# piezo-button-sheet1.net
KiCad netlist of a schematic drawn in Altium Designer
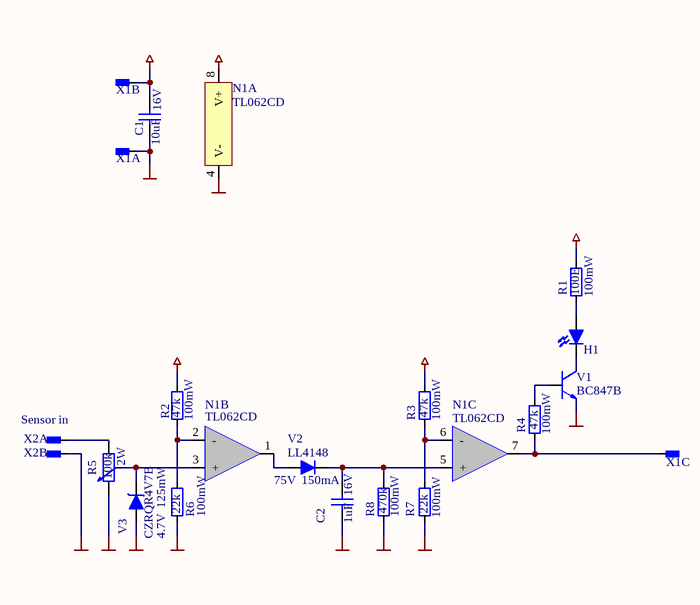
[diagram p0: piezo-button-sheet1.SchDoc]

(export (version "E")
  (design (tool "Eeschema 10.0.6"))
  (components
    (comp (ref "C1")
      (value "C_SMD_CER_10U_16V_10%_X5R_0805")
      (footprint "SMD_0805")
      (description "SMD Capacitor")
      (fields (field (name "ALTIUM_VALUE") "10uF") (field (name "VALUE2") "16V"))
      (libsource (lib "C-Capacitor") (part "C_SMD_CER_10U_16V_10%_X5R_0805"))
    )
    (comp (ref "C2")
      (value "C_SMD_CER_1U_16V_10%_X5R_0603")
      (footprint "SMD_0603")
      (description "SMD Capacitor")
      (fields (field (name "ALTIUM_VALUE") "1uF") (field (name "VALUE2") "16V"))
      (libsource (lib "C-Capacitor") (part "C_SMD_CER_1U_16V_10%_X5R_0603"))
    )
    (comp (ref "H1")
      (value "H_SMD_LED_GREEN_1206")
      (footprint "SMD_1206_BOTTOM_ENTRY")
      (description "LED GREEN CLEAR 1206 REV MT SMD")
      (libsource (lib "H-Signaling device") (part "H_SMD_LED_GREEN_1206"))
    )
    (comp (ref "N1")
      (value "N_TL062CD_SOP-8")
      (footprint "SMD_SOP_8")
      (description "Low-power JFET dual operation amplifier")
      (fields (field (name "TYPE") "TL062CD"))
      (libsource (lib "N-Analog") (part "N_TL062CD_SOP-8"))
    )
    (comp (ref "R1")
      (value "R_SMD_THINFILM_100E_0W1_1%_50PPM_0603")
      (footprint "SMD_0603")
      (description "SMD Resistor")
      (fields (field (name "ALTIUM_VALUE") "100E") (field (name "VALUE2") "100mW"))
      (libsource (lib "R-Resistor") (part "R_SMD_THINFILM_100E_0W1_1%_50PPM_0603"))
    )
    (comp (ref "R2")
      (value "R_SMD_THINFILM_47K_0W1_1%_50PPM_0603")
      (footprint "SMD_0603")
      (description "SMD Resistor")
      (fields (field (name "ALTIUM_VALUE") "47k") (field (name "VALUE2") "100mW"))
      (libsource (lib "R-Resistor") (part "R_SMD_THINFILM_47K_0W1_1%_50PPM_0603"))
    )
    (comp (ref "R3")
      (value "R_SMD_THINFILM_47K_0W1_1%_50PPM_0603")
      (footprint "SMD_0603")
      (description "SMD Resistor")
      (fields (field (name "ALTIUM_VALUE") "47k") (field (name "VALUE2") "100mW"))
      (libsource (lib "R-Resistor") (part "R_SMD_THINFILM_47K_0W1_1%_50PPM_0603"))
    )
    (comp (ref "R4")
      (value "R_SMD_THINFILM_47K_0W1_1%_50PPM_0603")
      (footprint "SMD_0603")
      (description "SMD Resistor")
      (fields (field (name "ALTIUM_VALUE") "47k") (field (name "VALUE2") "100mW"))
      (libsource (lib "R-Resistor") (part "R_SMD_THINFILM_47K_0W1_1%_50PPM_0603"))
    )
    (comp (ref "R5")
      (value "R_THT_POT_100K_2W_10%_150PPM")
      (footprint "THT_CON_P2.54_D0.9_1X3")
      (description "POT 100K OHM 3/4\" RD CERM")
      (fields (field (name "ALTIUM_VALUE") "100k") (field (name "VALUE2") "2W"))
      (libsource (lib "R-Resistor") (part "R_THT_POT_100K_2W_10%_150PPM"))
    )
    (comp (ref "R6")
      (value "R_SMD_THINFILM_22K_0W1_1&_50PPM_0603")
      (footprint "SMD_0603")
      (description "SMD Resistor")
      (fields (field (name "ALTIUM_VALUE") "22k") (field (name "VALUE2") "100mW"))
      (libsource (lib "R-Resistor") (part "R_SMD_THINFILM_22K_0W1_1&_50PPM_0603"))
    )
    (comp (ref "R7")
      (value "R_SMD_THINFILM_22K_0W1_1&_50PPM_0603")
      (footprint "SMD_0603")
      (description "SMD Resistor")
      (fields (field (name "ALTIUM_VALUE") "22k") (field (name "VALUE2") "100mW"))
      (libsource (lib "R-Resistor") (part "R_SMD_THINFILM_22K_0W1_1&_50PPM_0603"))
    )
    (comp (ref "R8")
      (value "R_SMD_THINFILM_470K_0W1_1%_50PPM_0603")
      (footprint "SMD_0603")
      (description "SMD Resistor")
      (fields (field (name "ALTIUM_VALUE") "470k") (field (name "VALUE2") "100mW"))
      (libsource (lib "R-Resistor") (part "R_SMD_THINFILM_470K_0W1_1%_50PPM_0603"))
    )
    (comp (ref "V1")
      (value "V_SMD_TRANS_NPN_BC847B_50V_0A2_SOT-23-3")
      (footprint "SMD_SOT_23_3")
      (description "NPN Transistor")
      (fields (field (name "TYPE") "BC847B"))
      (libsource (lib "V-Semiconductors") (part "V_SMD_TRANS_NPN_BC847B_50V_0A2_SOT-23-3"))
    )
    (comp (ref "V2")
      (value "V_SMD_DIODE_LL4148_75V_0A15_SOD-80")
      (footprint "SMD_SOD_80P")
      (fields
        (field (name "TYPE") "LL4148")
        (field (name "ALTIUM_VALUE") "75V")
        (field (name "VALUE2") "150mA")
      )
      (libsource (lib "V-Semiconductors") (part "V_SMD_DIODE_LL4148_75V_0A15_SOD-80"))
    )
    (comp (ref "V3")
      (value "V_SMD_Z-DIODE_4V7_0W125_0402")
      (footprint "SMD_0402P")
      (description "Zener Diode")
      (fields
        (field (name "TYPE") "CZRQR4V7B")
        (field (name "ALTIUM_VALUE") "4.7V")
        (field (name "VALUE2") "125mW")
      )
      (libsource (lib "V-Semiconductors") (part "V_SMD_Z-DIODE_4V7_0W125_3%_0402"))
    )
    (comp (ref "X1")
      (value "X_CONNECTOR_P2.54_D0.9_1X3")
      (footprint "THT_CON_P2.54_D0.9_1X3")
      (description "Pitch 2.54, Diameter 0.9mm, 1 row, 3 columns")
      (libsource (lib "X-Connectors") (part "X_CONNECTOR_P2.54_D0.9_1X3"))
    )
    (comp (ref "X2")
      (value "X_CONNECTOR_P2.54_D0.9_1X2")
      (footprint "THT_CON_P2.54_D0.9_1X2")
      (description "Pitch 2.54, Diameter 0.9mm, 1 row, 2 columns")
      (libsource (lib "X-Connectors") (part "X_CONNECTOR_P2.54_D0.9_1X2"))
    )
  )
  (nets
    (net (code "1") (name "GND") (class "Default")
      (node (ref "C1") (pin "1") (pinfunction "1_1") (pintype "passive"))
      (node (ref "C2") (pin "1") (pinfunction "1_1") (pintype "passive"))
      (node (ref "N1") (pin "4") (pinfunction "V-_4") (pintype "passive"))
      (node (ref "R5") (pin "1") (pinfunction "NC_1") (pintype "passive"))
      (node (ref "R6") (pin "1") (pinfunction "1_1") (pintype "passive"))
      (node (ref "R7") (pin "1") (pinfunction "1_1") (pintype "passive"))
      (node (ref "R8") (pin "1") (pinfunction "1_1") (pintype "passive"))
      (node (ref "V1") (pin "2") (pinfunction "E_2") (pintype "passive"))
      (node (ref "V3") (pin "1") (pinfunction "1_1") (pintype "passive"))
      (node (ref "X1") (pin "1") (pinfunction "1_1") (pintype "passive"))
      (node (ref "X2") (pin "2") (pinfunction "2_2") (pintype "passive"))
    )
    (net (code "2") (name "Net-(H1-Pad1)") (class "Default")
      (node (ref "H1") (pin "1") (pinfunction "1_1") (pintype "passive"))
      (node (ref "R1") (pin "1") (pinfunction "1_1") (pintype "passive"))
    )
    (net (code "3") (name "Net-(N1B-+)") (class "Default")
      (node (ref "N1") (pin "3") (pinfunction "+_3") (pintype "passive"))
      (node (ref "R5") (pin "2") (pinfunction "NC_2") (pintype "passive"))
      (node (ref "V3") (pin "2") (pinfunction "2_2") (pintype "passive"))
    )
    (net (code "4") (name "Net-(N1B--)") (class "Default")
      (node (ref "N1") (pin "2") (pinfunction "-_2") (pintype "passive"))
      (node (ref "R2") (pin "1") (pinfunction "1_1") (pintype "passive"))
      (node (ref "R6") (pin "2") (pinfunction "2_2") (pintype "passive"))
    )
    (net (code "5") (name "Net-(N1B-OUT-A)") (class "Default")
      (node (ref "N1") (pin "1") (pinfunction "OUT-A_1") (pintype "passive"))
      (node (ref "V2") (pin "1") (pinfunction "1_1") (pintype "passive"))
    )
    (net (code "6") (name "Net-(N1C-+)") (class "Default")
      (node (ref "C2") (pin "2") (pinfunction "2_2") (pintype "passive"))
      (node (ref "N1") (pin "5") (pinfunction "+_5") (pintype "passive"))
      (node (ref "R8") (pin "2") (pinfunction "2_2") (pintype "passive"))
      (node (ref "V2") (pin "2") (pinfunction "2_2") (pintype "passive"))
    )
    (net (code "7") (name "Net-(N1C--)") (class "Default")
      (node (ref "N1") (pin "6") (pinfunction "-_6") (pintype "passive"))
      (node (ref "R3") (pin "1") (pinfunction "1_1") (pintype "passive"))
      (node (ref "R7") (pin "2") (pinfunction "2_2") (pintype "passive"))
    )
    (net (code "8") (name "Net-(N1C-OUT-B)") (class "Default")
      (node (ref "N1") (pin "7") (pinfunction "OUT-B_7") (pintype "passive"))
      (node (ref "R4") (pin "1") (pinfunction "1_1") (pintype "passive"))
      (node (ref "X1") (pin "3") (pinfunction "3_3") (pintype "passive"))
    )
    (net (code "9") (name "Net-(R5-NC-Pad3)") (class "Default")
      (node (ref "R5") (pin "3") (pinfunction "NC_3") (pintype "passive"))
      (node (ref "X2") (pin "1") (pinfunction "1_1") (pintype "passive"))
    )
    (net (code "10") (name "Net-(V1-B)") (class "Default")
      (node (ref "R4") (pin "2") (pinfunction "2_2") (pintype "passive"))
      (node (ref "V1") (pin "1") (pinfunction "B_1") (pintype "passive"))
    )
    (net (code "11") (name "Net-(V1-C)") (class "Default")
      (node (ref "H1") (pin "2") (pinfunction "2_2") (pintype "passive"))
      (node (ref "V1") (pin "3") (pinfunction "C_3") (pintype "passive"))
    )
    (net (code "12") (name "VCC") (class "Default")
      (node (ref "C1") (pin "2") (pinfunction "2_2") (pintype "passive"))
      (node (ref "N1") (pin "8") (pinfunction "V+_8") (pintype "passive"))
      (node (ref "R1") (pin "2") (pinfunction "2_2") (pintype "passive"))
      (node (ref "R2") (pin "2") (pinfunction "2_2") (pintype "passive"))
      (node (ref "R3") (pin "2") (pinfunction "2_2") (pintype "passive"))
      (node (ref "X1") (pin "2") (pinfunction "2_2") (pintype "passive"))
    )
  )
)
